# board.net
KiCad netlist of a schematic drawn in EAGLE
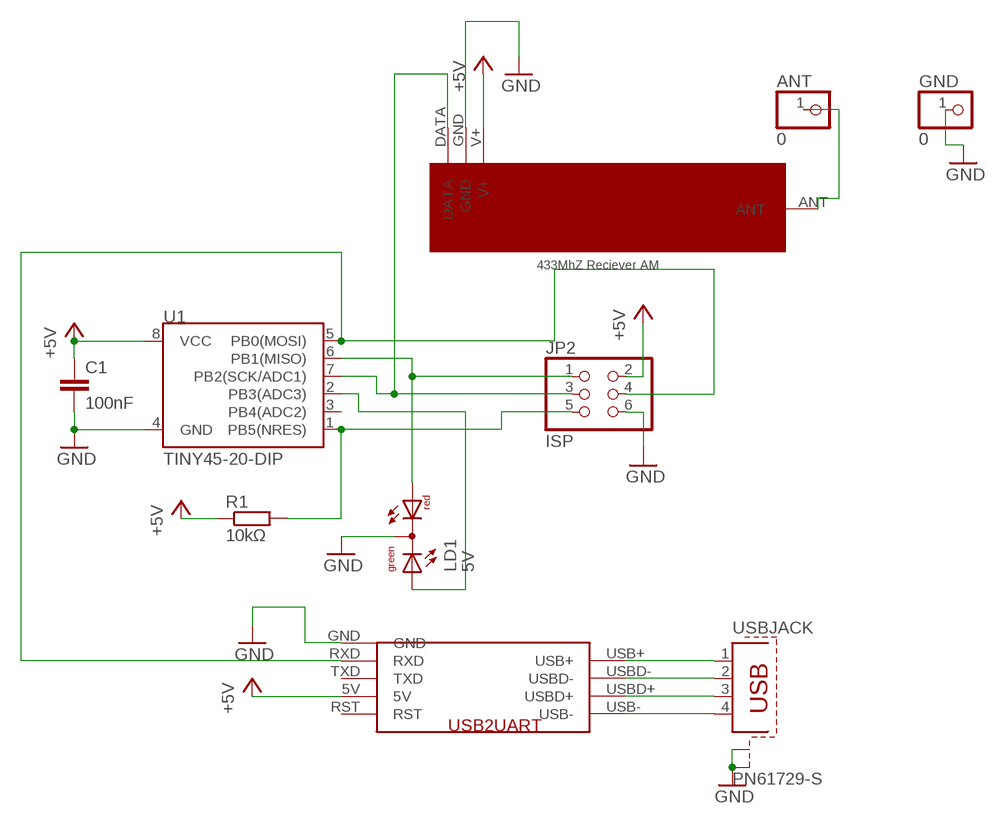
[diagram p0: schematic, sheet 1]

(export (version "E")
  (design (tool "Eeschema 10.0.6"))
  (components
    (comp (ref "ANT")
      (value "0")
      (footprint "eagle-import:1X01")
      (libsource (lib "eagle-import") (part "PINHD-1X1"))
    )
    (comp (ref "C1")
      (value "100nF")
      (footprint "eagle-import:C050-024X044")
      (libsource (lib "eagle-import") (part "C-EU050-024X044"))
    )
    (comp (ref "GND")
      (value "0")
      (footprint "eagle-import:1X01")
      (libsource (lib "eagle-import") (part "PINHD-1X1"))
    )
    (comp (ref "JP2")
      (value "ISP")
      (footprint "eagle-import:2X03")
      (libsource (lib "eagle-import") (part "PINHD-2X3"))
    )
    (comp (ref "LD1")
      (value "5V")
      (footprint "eagle-import:DUOLED-C-5MM")
      (libsource (lib "eagle-import") (part "DUOLED-RG-C"))
    )
    (comp (ref "R1")
      (value "10kΩ")
      (footprint "eagle-import:0411_15")
      (libsource (lib "eagle-import") (part "R-EU_0411/15"))
    )
    (comp (ref "U$1")
      (value "USB2UART")
      (footprint "eagle-import:USB2UART")
      (libsource (lib "eagle-import") (part "USB2UART"))
    )
    (comp (ref "U$2")
      (value "433MHZREC")
      (footprint "eagle-import:433MHZREC")
      (libsource (lib "eagle-import") (part "433MHZREC"))
    )
    (comp (ref "U1")
      (value "TINY45-20-DIP")
      (footprint "eagle-import:DIP08")
      (libsource (lib "eagle-import") (part "ATTINY45TINY45-20-DIP"))
    )
    (comp (ref "USBJACK")
      (value "PN61729-S")
      (footprint "eagle-import:PN61729-S")
      (libsource (lib "eagle-import") (part "PN61729-S"))
    )
  )
  (nets
    (net (code "1") (name "+5V") (class "Default")
      (node (ref "C1") (pin "1") (pinfunction "1_1") (pintype "passive"))
      (node (ref "JP2") (pin "2") (pinfunction "2_2") (pintype "passive"))
      (node (ref "R1") (pin "1") (pinfunction "1_1") (pintype "passive"))
      (node (ref "U$1") (pin "5V") (pinfunction "5V_5V") (pintype "bidirectional"))
      (node (ref "U$2") (pin "V+") (pinfunction "V+_V+") (pintype "bidirectional"))
      (node (ref "U1") (pin "8") (pinfunction "VCC_8") (pintype "bidirectional"))
    )
    (net (code "2") (name "GND") (class "Default")
      (node (ref "C1") (pin "2") (pinfunction "2_2") (pintype "passive"))
      (node (ref "GND") (pin "1") (pinfunction "1_1") (pintype "passive"))
      (node (ref "JP2") (pin "6") (pinfunction "6_6") (pintype "passive"))
      (node (ref "LD1") (pin "C") (pinfunction "C_C") (pintype "passive"))
      (node (ref "U$1") (pin "GND") (pinfunction "GND_GND") (pintype "bidirectional"))
      (node (ref "U$2") (pin "GND") (pinfunction "GND_GND") (pintype "bidirectional"))
      (node (ref "U1") (pin "4") (pinfunction "GND_4") (pintype "bidirectional"))
      (node (ref "USBJACK") (pin "S1") (pinfunction "S1_S1") (pintype "passive"))
      (node (ref "USBJACK") (pin "S2") (pinfunction "S2_S2") (pintype "passive"))
    )
    (net (code "3") (name "Net-(ANT-Pad1)") (class "Default")
      (node (ref "ANT") (pin "1") (pinfunction "1_1") (pintype "passive"))
      (node (ref "U$2") (pin "ANT") (pinfunction "ANT_ANT") (pintype "bidirectional"))
    )
    (net (code "4") (name "Net-(LD1-AG)") (class "Default")
      (node (ref "LD1") (pin "AX") (pinfunction "AG_AX") (pintype "passive"))
      (node (ref "U1") (pin "2") (pinfunction "PB3(ADC3)_2") (pintype "bidirectional"))
    )
    (net (code "5") (name "Net-(U$1-PadUSB+)") (class "Default")
      (node (ref "U$1") (pin "USB+") (pinfunction "USB+_USB+") (pintype "bidirectional"))
      (node (ref "USBJACK") (pin "1") (pinfunction "1_1") (pintype "passive"))
    )
    (net (code "6") (name "Net-(U$1-PadUSB-)") (class "Default")
      (node (ref "U$1") (pin "USB-") (pinfunction "USB-_USB-") (pintype "bidirectional"))
      (node (ref "USBJACK") (pin "4") (pinfunction "4_4") (pintype "passive"))
    )
    (net (code "7") (name "Net-(U$1-PadUSBD+)") (class "Default")
      (node (ref "U$1") (pin "USBD+") (pinfunction "USBD+_USBD+") (pintype "bidirectional"))
      (node (ref "USBJACK") (pin "3") (pinfunction "3_3") (pintype "passive"))
    )
    (net (code "8") (name "Net-(U$1-PadUSBD-)") (class "Default")
      (node (ref "U$1") (pin "USBD-") (pinfunction "USBD-_USBD-") (pintype "bidirectional"))
      (node (ref "USBJACK") (pin "2") (pinfunction "2_2") (pintype "passive"))
    )
    (net (code "9") (name "Net-(U1-PB0(MOSI))") (class "Default")
      (node (ref "JP2") (pin "4") (pinfunction "4_4") (pintype "passive"))
      (node (ref "U$1") (pin "RXD") (pinfunction "RXD_RXD") (pintype "bidirectional"))
      (node (ref "U1") (pin "5") (pinfunction "PB0(MOSI)_5") (pintype "bidirectional"))
    )
    (net (code "10") (name "Net-(U1-PB1(MISO))") (class "Default")
      (node (ref "JP2") (pin "1") (pinfunction "1_1") (pintype "passive"))
      (node (ref "LD1") (pin "AR") (pinfunction "AR_AR") (pintype "passive"))
      (node (ref "U1") (pin "6") (pinfunction "PB1(MISO)_6") (pintype "bidirectional"))
    )
    (net (code "11") (name "Net-(U1-PB2(SCK{slash}ADC1))") (class "Default")
      (node (ref "JP2") (pin "3") (pinfunction "3_3") (pintype "passive"))
      (node (ref "U$2") (pin "DATA") (pinfunction "DATA_DATA") (pintype "bidirectional"))
      (node (ref "U1") (pin "7") (pinfunction "PB2(SCK/ADC1)_7") (pintype "bidirectional"))
    )
    (net (code "12") (name "Net-(U1-PB5(NRES))") (class "Default")
      (node (ref "JP2") (pin "5") (pinfunction "5_5") (pintype "passive"))
      (node (ref "R1") (pin "2") (pinfunction "2_2") (pintype "passive"))
      (node (ref "U1") (pin "1") (pinfunction "PB5(NRES)_1") (pintype "bidirectional"))
    )
    (net (code "13") (name "unconnected-(U$1-PadRST)") (class "Default")
      (node (ref "U$1") (pin "RST") (pinfunction "RST_RST") (pintype "bidirectional"))
    )
    (net (code "14") (name "unconnected-(U$1-PadTXD)") (class "Default")
      (node (ref "U$1") (pin "TXD") (pinfunction "TXD_TXD") (pintype "bidirectional"))
    )
    (net (code "15") (name "unconnected-(U1-PB4(ADC2)-Pad3)") (class "Default")
      (node (ref "U1") (pin "3") (pinfunction "PB4(ADC2)_3") (pintype "bidirectional"))
    )
  )
)
